# 18_-_PCIE_MINI.net
KiCad netlist of a schematic drawn in Altium Designer
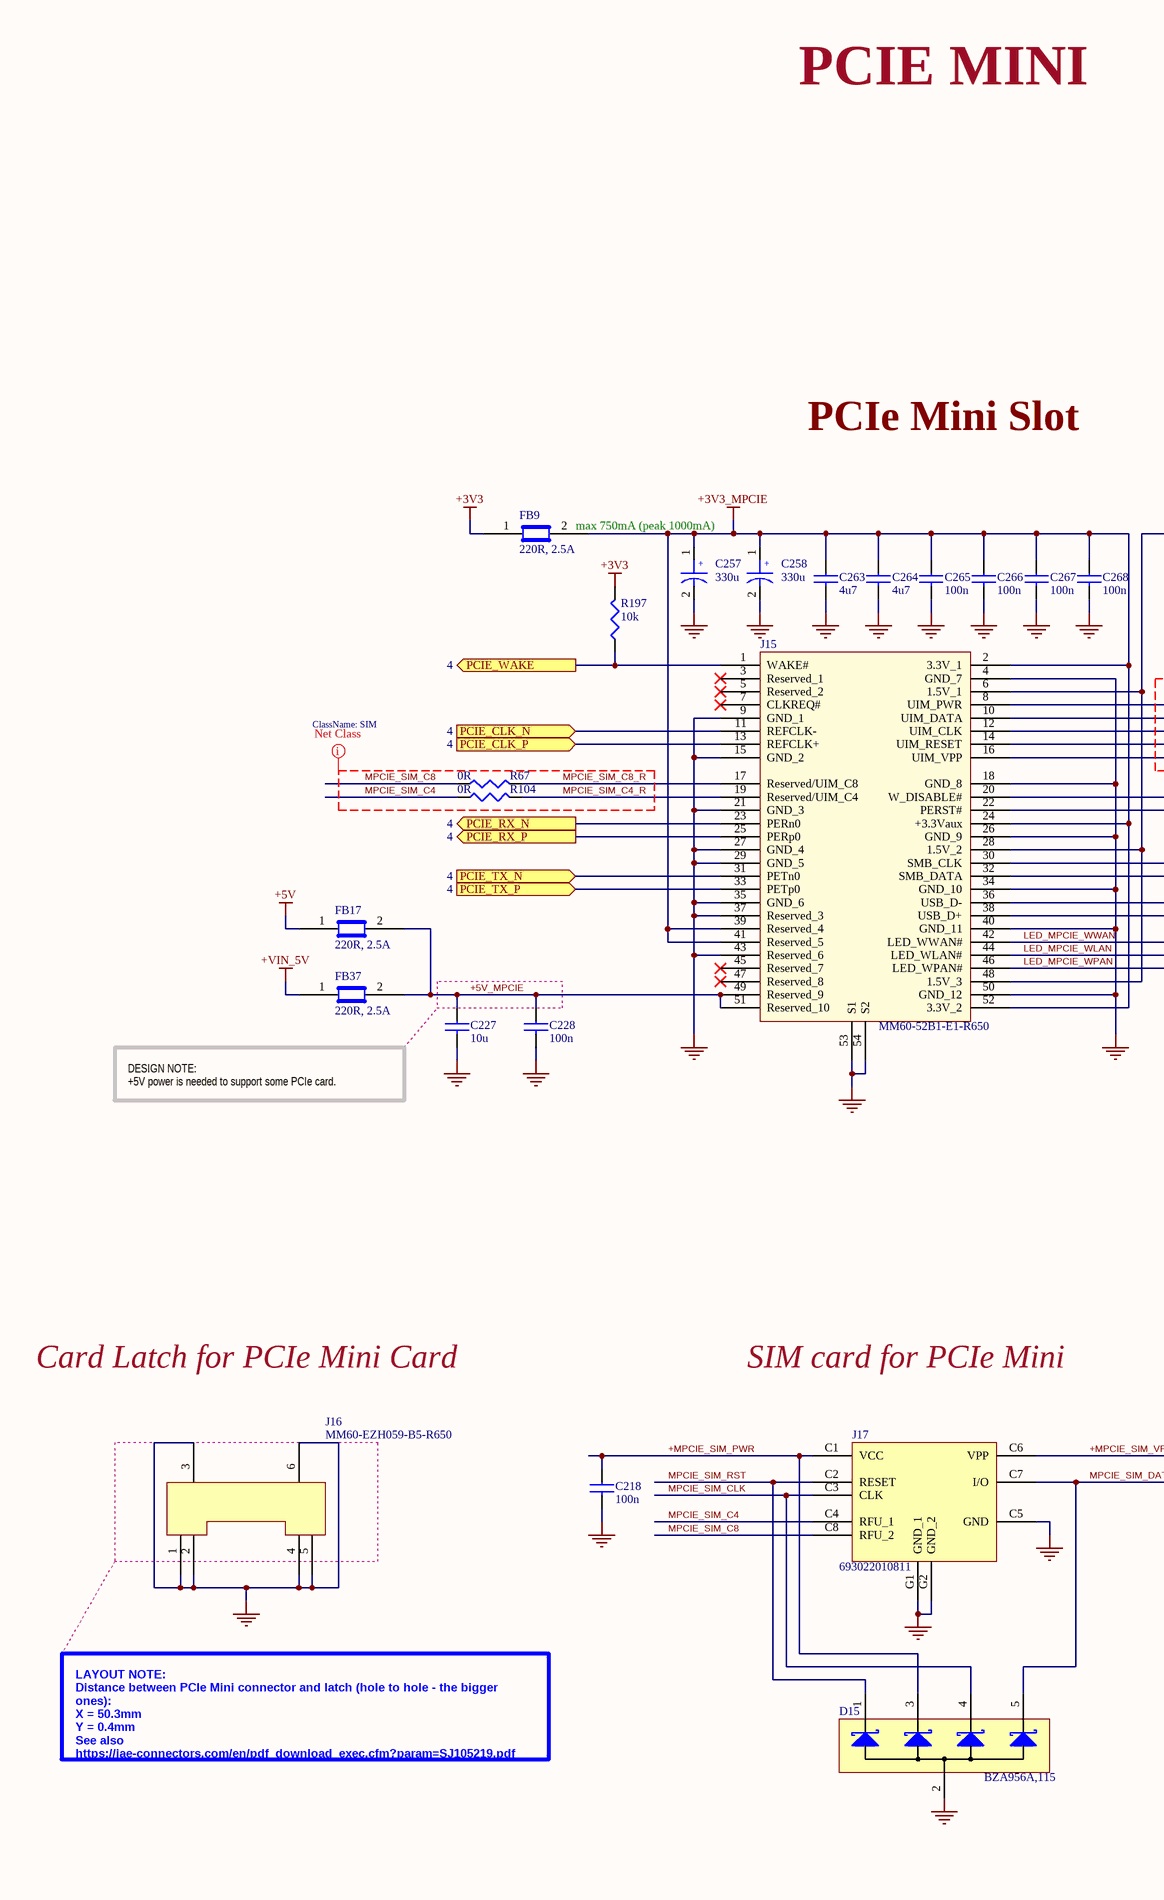
[diagram p0: [18] - PCIE MINI.SchDoc, left]
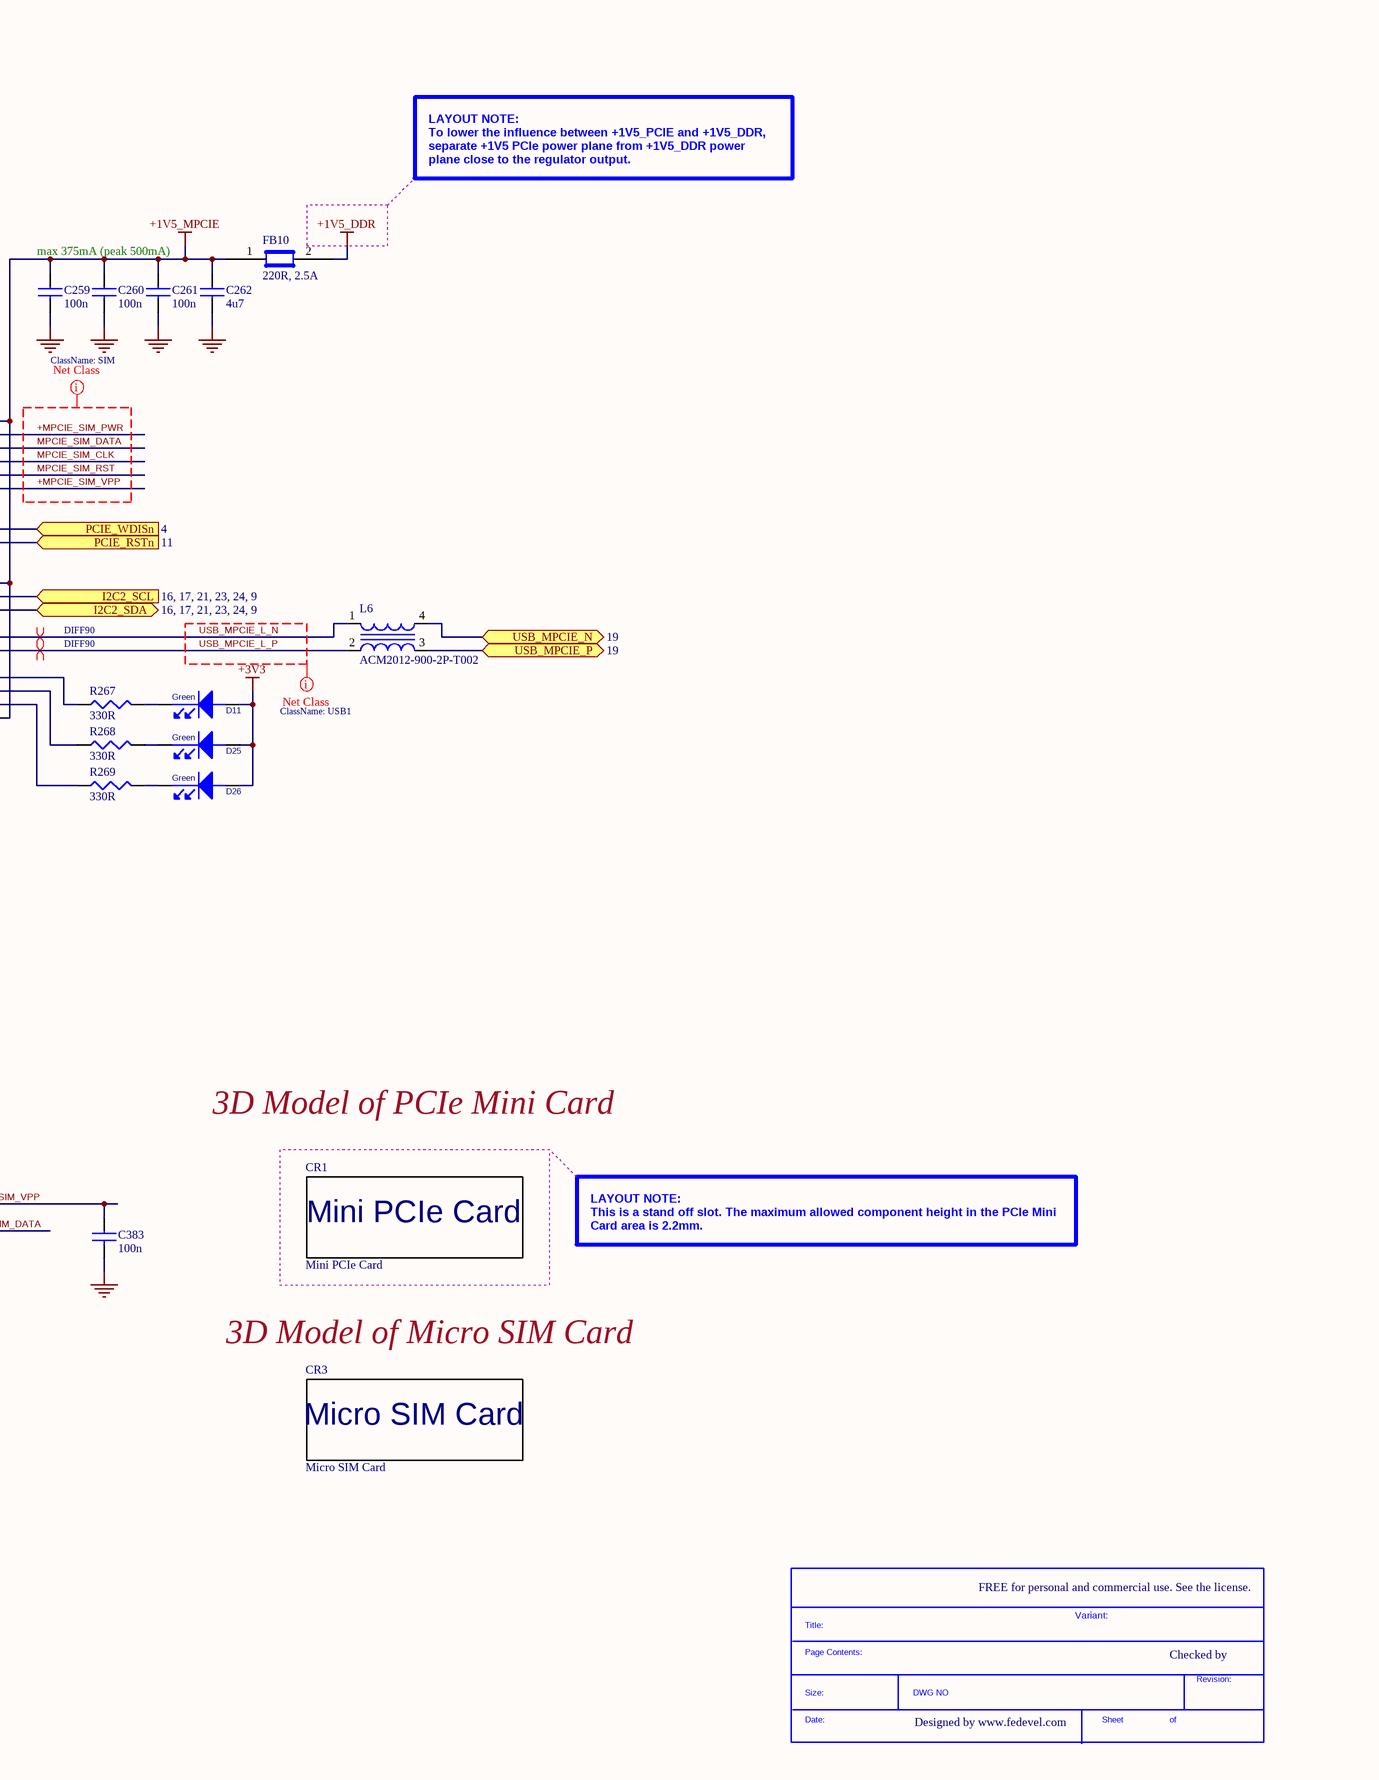
[diagram p1: [18] - PCIE MINI.SchDoc, right]

(export (version "E")
  (design (tool "Eeschema 10.0.6"))
  (components
    (comp (ref "C218")
      (value "100n")
      (footprint "C0402")
      (description "CAP CER .10UF 50V X5R 10% 0402")
      (fields
        (field (name "MANUFACTURER") "TDK Corporation")
        (field (name "MANUFACTURER PART NUMBER") "C1005X5R1H104K")
      )
      (libsource (lib "Integrated_Library_FEDEVEL_APR_2015") (part "C1005X5R1H104K"))
    )
    (comp (ref "C227")
      (value "10u")
      (footprint "C0603")
      (description "CAP CER 10UF 6.3V X5R 20% 0603")
      (fields
        (field (name "MANUFACTURER") "TDK Corporation")
        (field (name "MANUFACTURER PART NUMBER") "C1608X5R0J106M")
      )
      (libsource (lib "Integrated_Library_FEDEVEL_APR_2015") (part "C1608X5R0J106M"))
    )
    (comp (ref "C228")
      (value "100n")
      (footprint "C0402")
      (description "CAP CER .10UF 50V X5R 10% 0402")
      (fields
        (field (name "MANUFACTURER") "TDK Corporation")
        (field (name "MANUFACTURER PART NUMBER") "C1005X5R1H104K")
      )
      (libsource (lib "Integrated_Library_FEDEVEL_APR_2015") (part "C1005X5R1H104K"))
    )
    (comp (ref "C257")
      (value "330u")
      (footprint "C2917")
      (description "CAP TANT 330UF 6.3V 20% 2917")
      (fields
        (field (name "MANUFACTURER") "Kemet")
        (field (name "MANUFACTURER PART NUMBER") "T520D337M006ATE045")
        (field (name ".CREATOR") "MM")
      )
      (libsource (lib "Integrated_Library_FEDEVEL_APR_2015") (part "T520D337M006ATE045"))
    )
    (comp (ref "C258")
      (value "330u")
      (footprint "C2917")
      (description "CAP TANT 330UF 6.3V 20% 2917")
      (fields
        (field (name "MANUFACTURER") "Kemet")
        (field (name "MANUFACTURER PART NUMBER") "T520D337M006ATE045")
        (field (name ".CREATOR") "MM")
      )
      (libsource (lib "Integrated_Library_FEDEVEL_APR_2015") (part "T520D337M006ATE045"))
    )
    (comp (ref "C259")
      (value "100n")
      (footprint "C0402")
      (description "CAP CER .10UF 50V X5R 10% 0402")
      (fields
        (field (name "MANUFACTURER") "TDK Corporation")
        (field (name "MANUFACTURER PART NUMBER") "C1005X5R1H104K")
      )
      (libsource (lib "Integrated_Library_FEDEVEL_APR_2015") (part "C1005X5R1H104K"))
    )
    (comp (ref "C260")
      (value "100n")
      (footprint "C0402")
      (description "CAP CER .10UF 50V X5R 10% 0402")
      (fields
        (field (name "MANUFACTURER") "TDK Corporation")
        (field (name "MANUFACTURER PART NUMBER") "C1005X5R1H104K")
      )
      (libsource (lib "Integrated_Library_FEDEVEL_APR_2015") (part "C1005X5R1H104K"))
    )
    (comp (ref "C261")
      (value "100n")
      (footprint "C0402")
      (description "CAP CER .10UF 50V X5R 10% 0402")
      (fields
        (field (name "MANUFACTURER") "TDK Corporation")
        (field (name "MANUFACTURER PART NUMBER") "C1005X5R1H104K")
      )
      (libsource (lib "Integrated_Library_FEDEVEL_APR_2015") (part "C1005X5R1H104K"))
    )
    (comp (ref "C262")
      (value "4u7")
      (footprint "C0402")
      (description "CAP CER 4.7UF 10V 20% X5R 0402")
      (fields
        (field (name "MANUFACTURER") "TDK Corporation")
        (field (name "MANUFACTURER PART NUMBER") "C1005X5R1A475M")
      )
      (libsource (lib "Integrated_Library_FEDEVEL_APR_2015") (part "C1005X5R1A475M"))
    )
    (comp (ref "C263")
      (value "4u7")
      (footprint "C0402")
      (description "CAP CER 4.7UF 10V 20% X5R 0402")
      (fields
        (field (name "MANUFACTURER") "TDK Corporation")
        (field (name "MANUFACTURER PART NUMBER") "C1005X5R1A475M")
      )
      (libsource (lib "Integrated_Library_FEDEVEL_APR_2015") (part "C1005X5R1A475M"))
    )
    (comp (ref "C264")
      (value "4u7")
      (footprint "C0402")
      (description "CAP CER 4.7UF 10V 20% X5R 0402")
      (fields
        (field (name "MANUFACTURER") "TDK Corporation")
        (field (name "MANUFACTURER PART NUMBER") "C1005X5R1A475M")
      )
      (libsource (lib "Integrated_Library_FEDEVEL_APR_2015") (part "C1005X5R1A475M"))
    )
    (comp (ref "C265")
      (value "100n")
      (footprint "C0402")
      (description "CAP CER .10UF 50V X5R 10% 0402")
      (fields
        (field (name "MANUFACTURER") "TDK Corporation")
        (field (name "MANUFACTURER PART NUMBER") "C1005X5R1H104K")
      )
      (libsource (lib "Integrated_Library_FEDEVEL_APR_2015") (part "C1005X5R1H104K"))
    )
    (comp (ref "C266")
      (value "100n")
      (footprint "C0402")
      (description "CAP CER .10UF 50V X5R 10% 0402")
      (fields
        (field (name "MANUFACTURER") "TDK Corporation")
        (field (name "MANUFACTURER PART NUMBER") "C1005X5R1H104K")
      )
      (libsource (lib "Integrated_Library_FEDEVEL_APR_2015") (part "C1005X5R1H104K"))
    )
    (comp (ref "C267")
      (value "100n")
      (footprint "C0402")
      (description "CAP CER .10UF 50V X5R 10% 0402")
      (fields
        (field (name "MANUFACTURER") "TDK Corporation")
        (field (name "MANUFACTURER PART NUMBER") "C1005X5R1H104K")
      )
      (libsource (lib "Integrated_Library_FEDEVEL_APR_2015") (part "C1005X5R1H104K"))
    )
    (comp (ref "C268")
      (value "100n")
      (footprint "C0402")
      (description "CAP CER .10UF 50V X5R 10% 0402")
      (fields
        (field (name "MANUFACTURER") "TDK Corporation")
        (field (name "MANUFACTURER PART NUMBER") "C1005X5R1H104K")
      )
      (libsource (lib "Integrated_Library_FEDEVEL_APR_2015") (part "C1005X5R1H104K"))
    )
    (comp (ref "C383")
      (value "100n")
      (footprint "C0402")
      (description "CAP CER .10UF 50V X5R 10% 0402")
      (fields
        (field (name "MANUFACTURER") "TDK Corporation")
        (field (name "MANUFACTURER PART NUMBER") "C1005X5R1H104K")
      )
      (libsource (lib "Integrated_Library_FEDEVEL_APR_2015") (part "C1005X5R1H104K"))
    )
    (comp (ref "CR1")
      (value "Mini PCIe Card")
      (footprint "Mini_PCIe_full card")
      (description "Card MIni PCIe")
      (fields (field (name ".CREATOR") "MM"))
      (libsource (lib "Integrated_Library_FEDEVEL_APR_2015") (part "Card_Mini_PCIe"))
    )
    (comp (ref "CR3")
      (value "Micro SIM Card")
      (footprint "Micro_Sim_card")
      (description "Card Micro SIM")
      (fields (field (name ".CREATOR") "MM"))
      (libsource (lib "Integrated_Library_FEDEVEL_APR_2015") (part "Card_Micro_SIM"))
    )
    (comp (ref "D11")
      (value "Green")
      (footprint "LED_0603")
      (description "LED SMARTLED GREEN 570NM 0603")
      (fields
        (field (name "MANUFACTURER") "OSRAM Opto Semiconductors Inc")
        (field (name "MANUFACTURER PART NUMBER") "LG L29K-G2J1-24-Z")
      )
      (libsource (lib "Integrated_Library_FEDEVEL_APR_2015") (part "LG L29K-G2J1-24-Z"))
    )
    (comp (ref "D15")
      (value "BZA956A,115")
      (footprint "SOT665")
      (description "TVS ZENER QUAD 5.6V SOT665")
      (fields (field (name "MANUFACTURER") "NXP Semiconductors") (field (name ".CREATOR") "MM"))
      (libsource (lib "Integrated_Library_FEDEVEL_APR_2015") (part "BZA956A,115"))
    )
    (comp (ref "D25")
      (value "Green")
      (footprint "LED_0603")
      (description "LED SMARTLED GREEN 570NM 0603")
      (fields
        (field (name "MANUFACTURER") "OSRAM Opto Semiconductors Inc")
        (field (name "MANUFACTURER PART NUMBER") "LG L29K-G2J1-24-Z")
      )
      (libsource (lib "Integrated_Library_FEDEVEL_APR_2015") (part "LG L29K-G2J1-24-Z"))
    )
    (comp (ref "D26")
      (value "Green")
      (footprint "LED_0603")
      (description "LED SMARTLED GREEN 570NM 0603")
      (fields
        (field (name "MANUFACTURER") "OSRAM Opto Semiconductors Inc")
        (field (name "MANUFACTURER PART NUMBER") "LG L29K-G2J1-24-Z")
      )
      (libsource (lib "Integrated_Library_FEDEVEL_APR_2015") (part "LG L29K-G2J1-24-Z"))
    )
    (comp (ref "FB9")
      (value "220R, 2.5A")
      (footprint "C0603")
      (description "FERRITE CHIP 220 OHM 2500MA 0603")
      (fields
        (field (name "MANUFACTURER") "Murata Electronics North America")
        (field (name "MANUFACTURER PART NUMBER") "BLM18SG221TN1D")
      )
      (libsource (lib "Integrated_Library_FEDEVEL_APR_2015") (part "BLM18SG221TN1D"))
    )
    (comp (ref "FB10")
      (value "220R, 2.5A")
      (footprint "C0603")
      (description "FERRITE CHIP 220 OHM 2500MA 0603")
      (fields
        (field (name "MANUFACTURER") "Murata Electronics North America")
        (field (name "MANUFACTURER PART NUMBER") "BLM18SG221TN1D")
      )
      (libsource (lib "Integrated_Library_FEDEVEL_APR_2015") (part "BLM18SG221TN1D"))
    )
    (comp (ref "FB17")
      (value "220R, 2.5A")
      (footprint "C0603")
      (description "FERRITE CHIP 220 OHM 2500MA 0603")
      (fields
        (field (name "MANUFACTURER") "Murata Electronics North America")
        (field (name "MANUFACTURER PART NUMBER") "BLM18SG221TN1D")
      )
      (libsource (lib "Integrated_Library_FEDEVEL_APR_2015") (part "BLM18SG221TN1D"))
    )
    (comp (ref "FB37")
      (value "220R, 2.5A")
      (footprint "C0603")
      (description "FERRITE CHIP 220 OHM 2500MA 0603")
      (fields
        (field (name "MANUFACTURER") "Murata Electronics North America")
        (field (name "MANUFACTURER PART NUMBER") "BLM18SG221TN1D")
      )
      (libsource (lib "Integrated_Library_FEDEVEL_APR_2015") (part "BLM18SG221TN1D"))
    )
    (comp (ref "J15")
      (value "MM60-52B1-E1-R650")
      (footprint "MINI_PCIE_52PIN_CARD_CON")
      (description "CONN MINI EXPRESS CARD 52POS SMD")
      (fields (field (name "MANUFACTURER") "JAE Electronics") (field (name ".CREATOR") "MM"))
      (libsource (lib "Integrated_Library_FEDEVEL_APR_2015") (part "MM60-52B1-E1-R650"))
    )
    (comp (ref "J16")
      (value "MM60-EZH059-B5-R650")
      (footprint "MINI_PCIE_52PIN_CARD_LATCH")
      (description "CONN MINI EXPRESS CARD LATCH SMD")
      (fields (field (name "MANUFACTURER") "JAE Electronics") (field (name ".CREATOR") "MM"))
      (libsource (lib "Integrated_Library_FEDEVEL_APR_2015") (part "MM60-EZH059-B5-R650"))
    )
    (comp (ref "J17")
      (value "693022010811")
      (footprint "SIM_MICRO_HINGED")
      (description "CONN SMART CARD")
      (fields
        (field (name "MANUFACTURER") "Wurth Electronics Inc")
        (field (name ".CREATOR") "MM")
        (field (name ".CHECKED PCB") "MM")
        (field (name ".CHECKED SCH") "MM")
      )
      (libsource (lib "Integrated_Library_FEDEVEL_APR_2015") (part "693022010811"))
    )
    (comp (ref "L6")
      (value "ACM2012-900-2P-T002")
      (footprint "ACM2012")
      (description "CHOKE COMM MODE 90 OHM .4A SMD")
      (fields (field (name "MANUFACTURER") "TDK Corporation") (field (name "TOLERANCE") "±1%"))
      (libsource (lib "Integrated_Library_FEDEVEL_APR_2015") (part "ACM2012-900-2P-T002"))
    )
    (comp (ref "R67")
      (value "0R")
      (footprint "R0402")
      (description "RES 0.0 OHM 1/16W 0402 SMD")
      (fields
        (field (name "MANUFACTURER") "Yageo")
        (field (name "MANUFACTURER PART NUMBER") "RC0402JR-070RL")
      )
      (libsource (lib "Integrated_Library_FEDEVEL_APR_2015") (part "RC0402JR-070RL"))
    )
    (comp (ref "R104")
      (value "0R")
      (footprint "R0402")
      (description "RES 0.0 OHM 1/16W 0402 SMD")
      (fields
        (field (name "MANUFACTURER") "Yageo")
        (field (name "MANUFACTURER PART NUMBER") "RC0402JR-070RL")
      )
      (libsource (lib "Integrated_Library_FEDEVEL_APR_2015") (part "RC0402JR-070RL"))
    )
    (comp (ref "R197")
      (value "10k")
      (footprint "R0402")
      (description "RES 10.0K OHM 1/16W 1% 0402 SMD")
      (fields
        (field (name "MANUFACTURER") "Yageo")
        (field (name "MANUFACTURER PART NUMBER") "RC0402FR-0710KL")
      )
      (libsource (lib "Integrated_Library_FEDEVEL_APR_2015") (part "RC0402FR-0710KL"))
    )
    (comp (ref "R267")
      (value "330R")
      (footprint "R0402")
      (description "RES 330 OHM 1/16W 1% 0402 SMD")
      (fields
        (field (name "MANUFACTURER") "Vishay Dale")
        (field (name "MANUFACTURER PART NUMBER") "CRCW0402330RFKED")
      )
      (libsource (lib "Integrated_Library_FEDEVEL_APR_2015") (part "CRCW0402330RFKED"))
    )
    (comp (ref "R268")
      (value "330R")
      (footprint "R0402")
      (description "RES 330 OHM 1/16W 1% 0402 SMD")
      (fields
        (field (name "MANUFACTURER") "Vishay Dale")
        (field (name "MANUFACTURER PART NUMBER") "CRCW0402330RFKED")
      )
      (libsource (lib "Integrated_Library_FEDEVEL_APR_2015") (part "CRCW0402330RFKED"))
    )
    (comp (ref "R269")
      (value "330R")
      (footprint "R0402")
      (description "RES 330 OHM 1/16W 1% 0402 SMD")
      (fields
        (field (name "MANUFACTURER") "Vishay Dale")
        (field (name "MANUFACTURER PART NUMBER") "CRCW0402330RFKED")
      )
      (libsource (lib "Integrated_Library_FEDEVEL_APR_2015") (part "CRCW0402330RFKED"))
    )
  )
  (nets
    (net (code "1") (name "+1V5_DDR") (class "Default")
      (node (ref "FB10") (pin "2") (pinfunction "2_2") (pintype "passive"))
    )
    (net (code "2") (name "+1V5_MPCIE") (class "Default")
      (node (ref "C259") (pin "1") (pinfunction "1_1") (pintype "passive"))
      (node (ref "C260") (pin "1") (pinfunction "1_1") (pintype "passive"))
      (node (ref "C261") (pin "1") (pinfunction "1_1") (pintype "passive"))
      (node (ref "C262") (pin "1") (pinfunction "1_1") (pintype "passive"))
      (node (ref "FB10") (pin "1") (pinfunction "1_1") (pintype "passive"))
      (node (ref "J15") (pin "28") (pinfunction "1.5V_2_28") (pintype "passive"))
      (node (ref "J15") (pin "48") (pinfunction "1.5V_3_48") (pintype "passive"))
      (node (ref "J15") (pin "6") (pinfunction "1.5V_1_6") (pintype "passive"))
    )
    (net (code "3") (name "+3V3") (class "Default")
      (node (ref "D11") (pin "2") (pinfunction "ANODE_2") (pintype "passive"))
      (node (ref "D25") (pin "2") (pinfunction "ANODE_2") (pintype "passive"))
      (node (ref "D26") (pin "2") (pinfunction "ANODE_2") (pintype "passive"))
      (node (ref "FB9") (pin "1") (pinfunction "1_1") (pintype "passive"))
      (node (ref "R197") (pin "2") (pinfunction "2_2") (pintype "passive"))
    )
    (net (code "4") (name "+3V3_MPCIE") (class "Default")
      (node (ref "C257") (pin "1") (pinfunction "1_1") (pintype "passive"))
      (node (ref "C258") (pin "1") (pinfunction "1_1") (pintype "passive"))
      (node (ref "C263") (pin "1") (pinfunction "1_1") (pintype "passive"))
      (node (ref "C264") (pin "1") (pinfunction "1_1") (pintype "passive"))
      (node (ref "C265") (pin "1") (pinfunction "1_1") (pintype "passive"))
      (node (ref "C266") (pin "1") (pinfunction "1_1") (pintype "passive"))
      (node (ref "C267") (pin "1") (pinfunction "1_1") (pintype "passive"))
      (node (ref "C268") (pin "1") (pinfunction "1_1") (pintype "passive"))
      (node (ref "FB9") (pin "2") (pinfunction "2_2") (pintype "passive"))
      (node (ref "J15") (pin "2") (pinfunction "3.3V_1_2") (pintype "passive"))
      (node (ref "J15") (pin "24") (pinfunction "+3.3Vaux_24") (pintype "passive"))
      (node (ref "J15") (pin "39") (pinfunction "Reserved_4_39") (pintype "passive"))
      (node (ref "J15") (pin "41") (pinfunction "Reserved_5_41") (pintype "passive"))
      (node (ref "J15") (pin "52") (pinfunction "3.3V_2_52") (pintype "passive"))
    )
    (net (code "5") (name "+5V") (class "Default")
      (node (ref "FB17") (pin "1") (pinfunction "1_1") (pintype "passive"))
    )
    (net (code "6") (name "+VIN_5V") (class "Default")
      (node (ref "FB37") (pin "1") (pinfunction "1_1") (pintype "passive"))
    )
    (net (code "7") (name "/+5V_MPCIE") (class "Default")
      (node (ref "C227") (pin "1") (pinfunction "1_1") (pintype "passive"))
      (node (ref "C228") (pin "1") (pinfunction "1_1") (pintype "passive"))
      (node (ref "FB17") (pin "2") (pinfunction "2_2") (pintype "passive"))
      (node (ref "FB37") (pin "2") (pinfunction "2_2") (pintype "passive"))
      (node (ref "J15") (pin "49") (pinfunction "Reserved_9_49") (pintype "passive"))
      (node (ref "J15") (pin "51") (pinfunction "Reserved_10_51") (pintype "passive"))
    )
    (net (code "8") (name "/+MPCIE_SIM_PWR") (class "Default")
      (node (ref "C218") (pin "1") (pinfunction "1_1") (pintype "passive"))
      (node (ref "D15") (pin "3") (pinfunction "3_3") (pintype "passive"))
      (node (ref "J15") (pin "8") (pinfunction "UIM_PWR_8") (pintype "passive"))
      (node (ref "J17") (pin "C1") (pinfunction "VCC_C1") (pintype "passive"))
    )
    (net (code "9") (name "/+MPCIE_SIM_VPP") (class "Default")
      (node (ref "C383") (pin "1") (pinfunction "1_1") (pintype "passive"))
      (node (ref "J15") (pin "16") (pinfunction "UIM_VPP_16") (pintype "passive"))
      (node (ref "J17") (pin "C6") (pinfunction "VPP_C6") (pintype "passive"))
    )
    (net (code "10") (name "/I2C2_SCL") (class "Default")
      (node (ref "J15") (pin "30") (pinfunction "SMB_CLK_30") (pintype "passive"))
    )
    (net (code "11") (name "/I2C2_SDA") (class "Default")
      (node (ref "J15") (pin "32") (pinfunction "SMB_DATA_32") (pintype "passive"))
    )
    (net (code "12") (name "/LED_MPCIE_WLAN") (class "Default")
      (node (ref "J15") (pin "44") (pinfunction "LED_WLAN#_44") (pintype "passive"))
      (node (ref "R268") (pin "1") (pinfunction "1_1") (pintype "passive"))
    )
    (net (code "13") (name "/LED_MPCIE_WPAN") (class "Default")
      (node (ref "J15") (pin "46") (pinfunction "LED_WPAN#_46") (pintype "passive"))
      (node (ref "R269") (pin "1") (pinfunction "1_1") (pintype "passive"))
    )
    (net (code "14") (name "/LED_MPCIE_WWAN") (class "Default")
      (node (ref "J15") (pin "42") (pinfunction "LED_WWAN#_42") (pintype "passive"))
      (node (ref "R267") (pin "1") (pinfunction "1_1") (pintype "passive"))
    )
    (net (code "15") (name "/MPCIE_SIM_C4") (class "Default")
      (node (ref "J17") (pin "C4") (pinfunction "RFU_1_C4") (pintype "passive"))
      (node (ref "R104") (pin "1") (pinfunction "1_1") (pintype "passive"))
    )
    (net (code "16") (name "/MPCIE_SIM_C4_R") (class "Default")
      (node (ref "J15") (pin "19") (pinfunction "Reserved/UIM_C4_19") (pintype "passive"))
      (node (ref "R104") (pin "2") (pinfunction "2_2") (pintype "passive"))
    )
    (net (code "17") (name "/MPCIE_SIM_C8") (class "Default")
      (node (ref "J17") (pin "C8") (pinfunction "RFU_2_C8") (pintype "passive"))
      (node (ref "R67") (pin "1") (pinfunction "1_1") (pintype "passive"))
    )
    (net (code "18") (name "/MPCIE_SIM_C8_R") (class "Default")
      (node (ref "J15") (pin "17") (pinfunction "Reserved/UIM_C8_17") (pintype "passive"))
      (node (ref "R67") (pin "2") (pinfunction "2_2") (pintype "passive"))
    )
    (net (code "19") (name "/MPCIE_SIM_CLK") (class "Default")
      (node (ref "D15") (pin "4") (pinfunction "4_4") (pintype "passive"))
      (node (ref "J15") (pin "12") (pinfunction "UIM_CLK_12") (pintype "passive"))
      (node (ref "J17") (pin "C3") (pinfunction "CLK_C3") (pintype "passive"))
    )
    (net (code "20") (name "/MPCIE_SIM_DATA") (class "Default")
      (node (ref "D15") (pin "5") (pinfunction "5_5") (pintype "passive"))
      (node (ref "J15") (pin "10") (pinfunction "UIM_DATA_10") (pintype "passive"))
      (node (ref "J17") (pin "C7") (pinfunction "I/O_C7") (pintype "passive"))
    )
    (net (code "21") (name "/MPCIE_SIM_RST") (class "Default")
      (node (ref "D15") (pin "1") (pinfunction "1_1") (pintype "passive"))
      (node (ref "J15") (pin "14") (pinfunction "UIM_RESET_14") (pintype "passive"))
      (node (ref "J17") (pin "C2") (pinfunction "RESET_C2") (pintype "passive"))
    )
    (net (code "22") (name "/PCIE_CLK_N") (class "Default")
      (node (ref "J15") (pin "11") (pinfunction "REFCLK-_11") (pintype "passive"))
    )
    (net (code "23") (name "/PCIE_CLK_P") (class "Default")
      (node (ref "J15") (pin "13") (pinfunction "REFCLK+_13") (pintype "passive"))
    )
    (net (code "24") (name "/PCIE_RSTn") (class "Default")
      (node (ref "J15") (pin "22") (pinfunction "PERST#_22") (pintype "passive"))
    )
    (net (code "25") (name "/PCIE_RX_N") (class "Default")
      (node (ref "J15") (pin "23") (pinfunction "PERn0_23") (pintype "passive"))
    )
    (net (code "26") (name "/PCIE_RX_P") (class "Default")
      (node (ref "J15") (pin "25") (pinfunction "PERp0_25") (pintype "passive"))
    )
    (net (code "27") (name "/PCIE_TX_N") (class "Default")
      (node (ref "J15") (pin "31") (pinfunction "PETn0_31") (pintype "passive"))
    )
    (net (code "28") (name "/PCIE_TX_P") (class "Default")
      (node (ref "J15") (pin "33") (pinfunction "PETp0_33") (pintype "passive"))
    )
    (net (code "29") (name "/PCIE_WAKE") (class "Default")
      (node (ref "J15") (pin "1") (pinfunction "WAKE#_1") (pintype "passive"))
      (node (ref "R197") (pin "1") (pinfunction "1_1") (pintype "passive"))
    )
    (net (code "30") (name "/PCIE_WDISn") (class "Default")
      (node (ref "J15") (pin "20") (pinfunction "W_DISABLE#_20") (pintype "passive"))
    )
    (net (code "31") (name "/USB_MPCIE_L_N") (class "Default")
      (node (ref "J15") (pin "36") (pinfunction "USB_D-_36") (pintype "passive"))
      (node (ref "L6") (pin "1") (pinfunction "1_1") (pintype "passive"))
    )
    (net (code "32") (name "/USB_MPCIE_L_P") (class "Default")
      (node (ref "J15") (pin "38") (pinfunction "USB_D+_38") (pintype "passive"))
      (node (ref "L6") (pin "2") (pinfunction "2_2") (pintype "passive"))
    )
    (net (code "33") (name "/USB_MPCIE_N") (class "Default")
      (node (ref "L6") (pin "4") (pinfunction "4_4") (pintype "passive"))
    )
    (net (code "34") (name "/USB_MPCIE_P") (class "Default")
      (node (ref "L6") (pin "3") (pinfunction "3_3") (pintype "passive"))
    )
    (net (code "35") (name "GND") (class "Default")
      (node (ref "C218") (pin "2") (pinfunction "2_2") (pintype "passive"))
      (node (ref "C227") (pin "2") (pinfunction "2_2") (pintype "passive"))
      (node (ref "C228") (pin "2") (pinfunction "2_2") (pintype "passive"))
      (node (ref "C257") (pin "2") (pinfunction "2_2") (pintype "passive"))
      (node (ref "C258") (pin "2") (pinfunction "2_2") (pintype "passive"))
      (node (ref "C259") (pin "2") (pinfunction "2_2") (pintype "passive"))
      (node (ref "C260") (pin "2") (pinfunction "2_2") (pintype "passive"))
      (node (ref "C261") (pin "2") (pinfunction "2_2") (pintype "passive"))
      (node (ref "C262") (pin "2") (pinfunction "2_2") (pintype "passive"))
      (node (ref "C263") (pin "2") (pinfunction "2_2") (pintype "passive"))
      (node (ref "C264") (pin "2") (pinfunction "2_2") (pintype "passive"))
      (node (ref "C265") (pin "2") (pinfunction "2_2") (pintype "passive"))
      (node (ref "C266") (pin "2") (pinfunction "2_2") (pintype "passive"))
      (node (ref "C267") (pin "2") (pinfunction "2_2") (pintype "passive"))
      (node (ref "C268") (pin "2") (pinfunction "2_2") (pintype "passive"))
      (node (ref "C383") (pin "2") (pinfunction "2_2") (pintype "passive"))
      (node (ref "D15") (pin "2") (pinfunction "2_2") (pintype "passive"))
      (node (ref "J15") (pin "15") (pinfunction "GND_2_15") (pintype "passive"))
      (node (ref "J15") (pin "18") (pinfunction "GND_8_18") (pintype "passive"))
      (node (ref "J15") (pin "21") (pinfunction "GND_3_21") (pintype "passive"))
      (node (ref "J15") (pin "26") (pinfunction "GND_9_26") (pintype "passive"))
      (node (ref "J15") (pin "27") (pinfunction "GND_4_27") (pintype "passive"))
      (node (ref "J15") (pin "29") (pinfunction "GND_5_29") (pintype "passive"))
      (node (ref "J15") (pin "34") (pinfunction "GND_10_34") (pintype "passive"))
      (node (ref "J15") (pin "35") (pinfunction "GND_6_35") (pintype "passive"))
      (node (ref "J15") (pin "37") (pinfunction "Reserved_3_37") (pintype "passive"))
      (node (ref "J15") (pin "4") (pinfunction "GND_7_4") (pintype "passive"))
      (node (ref "J15") (pin "40") (pinfunction "GND_11_40") (pintype "passive"))
      (node (ref "J15") (pin "43") (pinfunction "Reserved_6_43") (pintype "passive"))
      (node (ref "J15") (pin "50") (pinfunction "GND_12_50") (pintype "passive"))
      (node (ref "J15") (pin "53") (pinfunction "S1_53") (pintype "passive"))
      (node (ref "J15") (pin "54") (pinfunction "S2_54") (pintype "passive"))
      (node (ref "J15") (pin "9") (pinfunction "GND_1_9") (pintype "passive"))
      (node (ref "J16") (pin "1") (pinfunction "1_1") (pintype "passive"))
      (node (ref "J16") (pin "2") (pinfunction "2_2") (pintype "passive"))
      (node (ref "J16") (pin "3") (pinfunction "3_3") (pintype "passive"))
      (node (ref "J16") (pin "4") (pinfunction "4_4") (pintype "passive"))
      (node (ref "J16") (pin "5") (pinfunction "5_5") (pintype "passive"))
      (node (ref "J16") (pin "6") (pinfunction "6_6") (pintype "passive"))
      (node (ref "J17") (pin "C5") (pinfunction "GND_C5") (pintype "passive"))
      (node (ref "J17") (pin "G1") (pinfunction "GND_1_G1") (pintype "passive"))
      (node (ref "J17") (pin "G2") (pinfunction "GND_2_G2") (pintype "passive"))
    )
    (net (code "36") (name "Net-(D11-cathode)") (class "Default")
      (node (ref "D11") (pin "1") (pinfunction "cathode_1") (pintype "passive"))
      (node (ref "R267") (pin "2") (pinfunction "2_2") (pintype "passive"))
    )
    (net (code "37") (name "Net-(D25-cathode)") (class "Default")
      (node (ref "D25") (pin "1") (pinfunction "cathode_1") (pintype "passive"))
      (node (ref "R268") (pin "2") (pinfunction "2_2") (pintype "passive"))
    )
    (net (code "38") (name "Net-(D26-cathode)") (class "Default")
      (node (ref "D26") (pin "1") (pinfunction "cathode_1") (pintype "passive"))
      (node (ref "R269") (pin "2") (pinfunction "2_2") (pintype "passive"))
    )
    (net (code "39") (name "unconnected-(J15-CLKREQ#-Pad7)") (class "Default")
      (node (ref "J15") (pin "7") (pinfunction "CLKREQ#_7") (pintype "passive+no_connect"))
    )
    (net (code "40") (name "unconnected-(J15-Reserved_1-Pad3)") (class "Default")
      (node (ref "J15") (pin "3") (pinfunction "Reserved_1_3") (pintype "passive+no_connect"))
    )
    (net (code "41") (name "unconnected-(J15-Reserved_2-Pad5)") (class "Default")
      (node (ref "J15") (pin "5") (pinfunction "Reserved_2_5") (pintype "passive+no_connect"))
    )
    (net (code "42") (name "unconnected-(J15-Reserved_7-Pad45)") (class "Default")
      (node (ref "J15") (pin "45") (pinfunction "Reserved_7_45") (pintype "passive+no_connect"))
    )
    (net (code "43") (name "unconnected-(J15-Reserved_8-Pad47)") (class "Default")
      (node (ref "J15") (pin "47") (pinfunction "Reserved_8_47") (pintype "passive+no_connect"))
    )
  )
)
